# Vref.net
KiCad netlist of a schematic drawn in Altium Designer
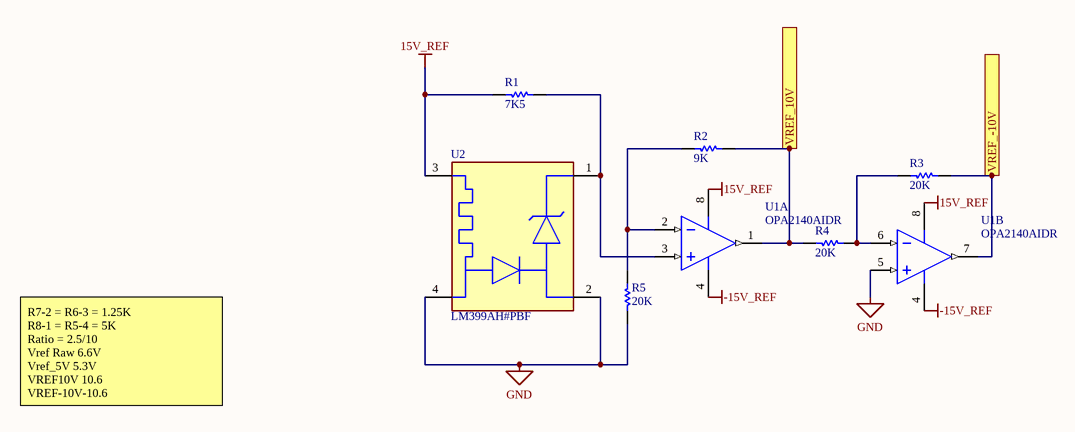
[diagram p0: Vref.SchDoc]

(export (version "E")
  (design (tool "Eeschema 10.0.6"))
  (components
    (comp (ref "R1")
      (value "7K5")
      (footprint "RESC2013X60X35ML10T20")
      (description "Chip Resistor, 1 KOhm, +/- 1%, 125 mW, -55 to 155 degC, 0805 (2012 Metric), RoHS, Tape and Reel")
      (fields (field (name "TOLERANCE") "1%") (field (name "MANUFACTURER") "Yageo"))
      (libsource (lib "Altium Content Vault") (part "RES-2"))
    )
    (comp (ref "R2")
      (value "9K")
      (footprint "RESC2013X60X35ML10T20")
      (description "Chip Resistor, 1 KOhm, +/- 1%, 125 mW, -55 to 155 degC, 0805 (2012 Metric), RoHS, Tape and Reel")
      (fields (field (name "TOLERANCE") "1%") (field (name "MANUFACTURER") "Yageo"))
      (libsource (lib "Altium Content Vault") (part "RES-2"))
    )
    (comp (ref "R3")
      (value "20K")
      (footprint "RESC2013X60X35ML10T20")
      (description "Chip Resistor, 1 KOhm, +/- 1%, 125 mW, -55 to 155 degC, 0805 (2012 Metric), RoHS, Tape and Reel")
      (fields (field (name "TOLERANCE") "1%") (field (name "MANUFACTURER") "Yageo"))
      (libsource (lib "Altium Content Vault") (part "RES-2"))
    )
    (comp (ref "R4")
      (value "20K")
      (footprint "RESC2013X60X35ML10T20")
      (description "Chip Resistor, 1 KOhm, +/- 1%, 125 mW, -55 to 155 degC, 0805 (2012 Metric), RoHS, Tape and Reel")
      (fields (field (name "TOLERANCE") "1%") (field (name "MANUFACTURER") "Yageo"))
      (libsource (lib "Altium Content Vault") (part "RES-2"))
    )
    (comp (ref "R5")
      (value "20K")
      (footprint "RESC2013X60X35ML10T20")
      (description "Chip Resistor, 1 KOhm, +/- 1%, 125 mW, -55 to 155 degC, 0805 (2012 Metric), RoHS, Tape and Reel")
      (fields (field (name "TOLERANCE") "1%") (field (name "MANUFACTURER") "Yageo"))
      (libsource (lib "Altium Content Vault") (part "RES-2"))
    )
    (comp (ref "U1")
      (value "OPA2140AIDR")
      (footprint "D0008A_M")
      (fields (field (name "MANUFACTURER") "Texas Instruments"))
      (libsource (lib "Altium Content Vault") (part "TI-OPA-8_2"))
    )
    (comp (ref "U2")
      (value "LM399AH#PBF")
      (footprint "FP-H-4-05-08-1341-MFG")
      (description "IC VREF SHUNT 0.17% TO46-4")
      (fields (field (name "TOLERANCE") "2%"))
      (libsource (lib "Altium Content Vault") (part "5c7e1edee26e806ee10079c127ee9bb"))
    )
  )
  (nets
    (net (code "1") (name "-15V_REF") (class "Default")
      (node (ref "U1") (pin "4") (pinfunction "V-_4") (pintype "power_in"))
    )
    (net (code "2") (name "/VREF_-10V") (class "Default")
      (node (ref "R3") (pin "2") (pinfunction "2_2") (pintype "passive"))
      (node (ref "U1") (pin "7") (pinfunction "OUT_B_7") (pintype "output"))
    )
    (net (code "3") (name "/VREF_10V") (class "Default")
      (node (ref "R2") (pin "2") (pinfunction "2_2") (pintype "passive"))
      (node (ref "R4") (pin "1") (pinfunction "1_1") (pintype "passive"))
      (node (ref "U1") (pin "1") (pinfunction "OUT_A_1") (pintype "output"))
    )
    (net (code "4") (name "15V_REF") (class "Default")
      (node (ref "R1") (pin "2") (pinfunction "2_2") (pintype "passive"))
      (node (ref "U1") (pin "8") (pinfunction "V+_8") (pintype "power_in"))
      (node (ref "U2") (pin "3") (pinfunction "3_3") (pintype "passive"))
    )
    (net (code "5") (name "GND") (class "Default")
      (node (ref "R5") (pin "2") (pinfunction "2_2") (pintype "passive"))
      (node (ref "U1") (pin "5") (pinfunction "IN_B+_5") (pintype "input"))
      (node (ref "U2") (pin "2") (pinfunction "2_2") (pintype "passive"))
      (node (ref "U2") (pin "4") (pinfunction "4_4") (pintype "passive"))
    )
    (net (code "6") (name "Net-(U1A-IN_A+)") (class "Default")
      (node (ref "R1") (pin "1") (pinfunction "1_1") (pintype "passive"))
      (node (ref "U1") (pin "3") (pinfunction "IN_A+_3") (pintype "input"))
      (node (ref "U2") (pin "1") (pinfunction "1_1") (pintype "passive"))
    )
    (net (code "7") (name "Net-(U1A-IN_A-)") (class "Default")
      (node (ref "R2") (pin "1") (pinfunction "1_1") (pintype "passive"))
      (node (ref "R5") (pin "1") (pinfunction "1_1") (pintype "passive"))
      (node (ref "U1") (pin "2") (pinfunction "IN_A-_2") (pintype "input"))
    )
    (net (code "8") (name "Net-(U1B-IN_B-)") (class "Default")
      (node (ref "R3") (pin "1") (pinfunction "1_1") (pintype "passive"))
      (node (ref "R4") (pin "2") (pinfunction "2_2") (pintype "passive"))
      (node (ref "U1") (pin "6") (pinfunction "IN_B-_6") (pintype "input"))
    )
  )
)
